# Flash_STM32.net
KiCad netlist of a schematic drawn in Altium Designer
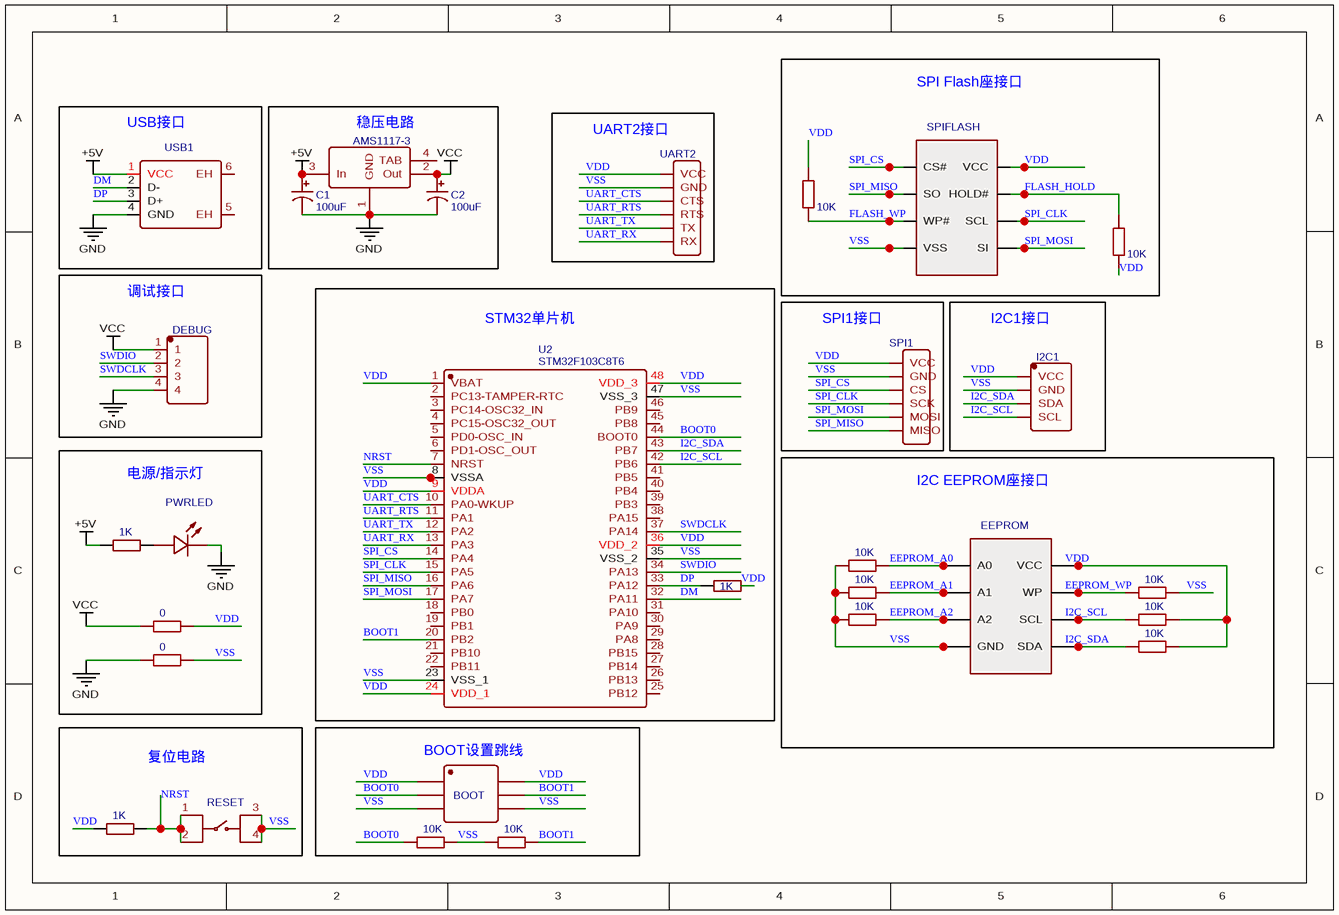
[diagram p0: Flash烧录器STM32版.schdoc]

(export (version "E")
  (design (tool "Eeschema 10.0.6"))
  (components
    (comp (ref "AMS1117-3")
      (value "AMS1117-3.3_C165482")
      (fields
        (field (name "BOM_SUPPLIER PART") "C165482")
        (field (name "BOM_MANUFACTURER PART") "AMS1117-3.3")
        (field (name "CONTRIBUTOR") "LCSC")
      )
      (libsource (lib "altium-import") (part "root_0_AMS1117-3.3_C165482_"))
    )
    (comp (ref "BOOT")
      (value "210S-2*3P L=11.6MMGold-plated black")
      (fields (field (name "BOM_SUPPLIER PART") "C124384") (field (name "CONTRIBUTOR") "LCSC"))
      (libsource (lib "altium-import") (part "root_0_210S-2*3P L=11.6MMGold-plated black_"))
    )
    (comp (ref "C1")
      (value "100uF")
      (fields
        (field (name "BOM_MANUFACTURER PART") "RVT1A101M0505")
        (field (name "BOM_SUPPLIER PART") "C3347")
      )
      (libsource (lib "altium-import") (part "root_0_100uF_"))
    )
    (comp (ref "C2")
      (value "100uF")
      (fields
        (field (name "BOM_MANUFACTURER PART") "RVT1A101M0505")
        (field (name "BOM_SUPPLIER PART") "C3347")
      )
      (libsource (lib "altium-import") (part "root_0_100uF_"))
    )
    (comp (ref "DEBUG")
      (value "MTP125-1104S1")
      (fields (field (name "BOM_SUPPLIER PART") "C358686") (field (name "CONTRIBUTOR") "LCSC"))
      (libsource (lib "altium-import") (part "root_0_MTP125-1104S1_"))
    )
    (comp (ref "EEPROM")
      (value "DS1009-08AT1NX-0A2")
      (fields (field (name "BOM_SUPPLIER PART") "C72124"))
      (libsource (lib "altium-import") (part "root_0_DS1009-08AT1NX-0A2_"))
    )
    (comp (ref "I2C1")
      (value "MTP125-1104S1")
      (fields (field (name "BOM_SUPPLIER PART") "C358686") (field (name "CONTRIBUTOR") "LCSC"))
      (libsource (lib "") (part "root_0_MTP125-1104S1__1"))
    )
    (comp (ref "PWRLED")
      (value "MHL3014SRTS")
      (fields (field (name "BOM_SUPPLIER PART") "C397053") (field (name "CONTRIBUTOR") "LCSC"))
      (libsource (lib "altium-import") (part "root_0_MHL3014SRTS_"))
    )
    (comp (ref "R1")
      (value "1K")
      (fields
        (field (name "BOM_MANUFACTURER PART") "0603WAF1001T5E")
        (field (name "BOM_SUPPLIER PART") "C21190")
      )
      (libsource (lib "altium-import") (part "root_0_1K_"))
    )
    (comp (ref "R2")
      (value "1K")
      (fields
        (field (name "BOM_MANUFACTURER PART") "0603WAF1001T5E")
        (field (name "BOM_SUPPLIER PART") "C21190")
      )
      (libsource (lib "altium-import") (part "root_0_1K_"))
    )
    (comp (ref "R3")
      (value "10K")
      (fields
        (field (name "BOM_SUPPLIER PART") "C237800")
        (field (name "BOM_MANUFACTURER PART") "RMCF1206JT10K0")
        (field (name "CONTRIBUTOR") "LCSC")
      )
      (libsource (lib "altium-import") (part "root_0_10K_"))
    )
    (comp (ref "R4")
      (value "10K")
      (fields
        (field (name "BOM_SUPPLIER PART") "C237800")
        (field (name "BOM_MANUFACTURER PART") "RMCF1206JT10K0")
        (field (name "CONTRIBUTOR") "LCSC")
      )
      (libsource (lib "altium-import") (part "root_0_10K_"))
    )
    (comp (ref "R5")
      (value "10K")
      (fields
        (field (name "BOM_SUPPLIER PART") "C237800")
        (field (name "BOM_MANUFACTURER PART") "RMCF1206JT10K0")
        (field (name "CONTRIBUTOR") "LCSC")
      )
      (libsource (lib "altium-import") (part "root_1_10K_"))
    )
    (comp (ref "R6")
      (value "10K")
      (fields
        (field (name "BOM_SUPPLIER PART") "C237800")
        (field (name "BOM_MANUFACTURER PART") "RMCF1206JT10K0")
        (field (name "CONTRIBUTOR") "LCSC")
      )
      (libsource (lib "altium-import") (part "root_1_10K_"))
    )
    (comp (ref "R7")
      (value "10K")
      (fields
        (field (name "BOM_SUPPLIER PART") "C237800")
        (field (name "BOM_MANUFACTURER PART") "RMCF1206JT10K0")
        (field (name "CONTRIBUTOR") "LCSC")
      )
      (libsource (lib "altium-import") (part "root_2_10K_"))
    )
    (comp (ref "R8")
      (value "10K")
      (fields
        (field (name "BOM_SUPPLIER PART") "C237800")
        (field (name "BOM_MANUFACTURER PART") "RMCF1206JT10K0")
        (field (name "CONTRIBUTOR") "LCSC")
      )
      (libsource (lib "altium-import") (part "root_2_10K_"))
    )
    (comp (ref "R9")
      (value "10K")
      (fields
        (field (name "BOM_SUPPLIER PART") "C237800")
        (field (name "BOM_MANUFACTURER PART") "RMCF1206JT10K0")
        (field (name "CONTRIBUTOR") "LCSC")
      )
      (libsource (lib "altium-import") (part "root_2_10K_"))
    )
    (comp (ref "R10")
      (value "10K")
      (fields
        (field (name "BOM_SUPPLIER PART") "C237800")
        (field (name "BOM_MANUFACTURER PART") "RMCF1206JT10K0")
        (field (name "CONTRIBUTOR") "LCSC")
      )
      (libsource (lib "altium-import") (part "root_2_10K_"))
    )
    (comp (ref "R11")
      (value "10K")
      (fields
        (field (name "BOM_SUPPLIER PART") "C237800")
        (field (name "BOM_MANUFACTURER PART") "RMCF1206JT10K0")
        (field (name "CONTRIBUTOR") "LCSC")
      )
      (libsource (lib "altium-import") (part "root_2_10K_"))
    )
    (comp (ref "R12")
      (value "10K")
      (fields
        (field (name "BOM_SUPPLIER PART") "C237800")
        (field (name "BOM_MANUFACTURER PART") "RMCF1206JT10K0")
        (field (name "CONTRIBUTOR") "LCSC")
      )
      (libsource (lib "altium-import") (part "root_2_10K_"))
    )
    (comp (ref "R13")
      (value "0")
      (fields
        (field (name "BOM_SUPPLIER PART") "C254574")
        (field (name "BOM_MANUFACTURER PART") "RM10FTN0")
        (field (name "CONTRIBUTOR") "LCSC")
      )
      (libsource (lib "altium-import") (part "root_0_0_"))
    )
    (comp (ref "R14")
      (value "0")
      (fields
        (field (name "BOM_SUPPLIER PART") "C254574")
        (field (name "BOM_MANUFACTURER PART") "RM10FTN0")
        (field (name "CONTRIBUTOR") "LCSC")
      )
      (libsource (lib "altium-import") (part "root_0_0_"))
    )
    (comp (ref "R15")
      (value "1K")
      (fields
        (field (name "BOM_MANUFACTURER PART") "0603WAF1001T5E")
        (field (name "BOM_SUPPLIER PART") "C21190")
      )
      (libsource (lib "altium-import") (part "root_0_1K_"))
    )
    (comp (ref "RESET")
      (value "K2-6639SP-C4SC-04")
      (fields (field (name "BOM_SUPPLIER PART") "C83206"))
      (libsource (lib "altium-import") (part "root_0_K2-6639SP-C4SC-04_"))
    )
    (comp (ref "SPI1")
      (value "Header-Male-2.54_1x6")
      (fields (field (name "BOM_SUPPLIER PART") "C37208"))
      (libsource (lib "altium-import") (part "root_0_Header-Male-2.54_1x6_"))
    )
    (comp (ref "SPIFLASH")
      (value "DS1009-08AT1NX-0A2")
      (fields (field (name "BOM_SUPPLIER PART") "C72124"))
      (libsource (lib "altium-import") (part "root_0_DS1009-08AT1NX-0A2_"))
    )
    (comp (ref "U2")
      (value "STM32F103C8T6")
      (fields (field (name "BOM_SUPPLIER PART") "C8734"))
      (libsource (lib "altium-import") (part "root_0_STM32F103C8T6_"))
    )
    (comp (ref "UART2")
      (value "Header-Male-2.54_1x6")
      (fields (field (name "BOM_SUPPLIER PART") "C37208"))
      (libsource (lib "altium-import") (part "root_0_Header-Male-2.54_1x6_"))
    )
    (comp (ref "USB1")
      (value "USB-05")
      (fields (field (name "BOM_SUPPLIER PART") "C112454") (field (name "CONTRIBUTOR") "LCSC"))
      (libsource (lib "altium-import") (part "root_0_USB-05_"))
    )
  )
  (nets
    (net (code "1") (name "+5V") (class "Default")
      (node (ref "AMS1117-3") (pin "3") (pinfunction "In_3") (pintype "passive"))
      (node (ref "C1") (pin "1") (pinfunction "1_1") (pintype "passive"))
      (node (ref "R1") (pin "1") (pinfunction "1_1") (pintype "passive"))
      (node (ref "USB1") (pin "1") (pinfunction "VCC_1") (pintype "passive"))
    )
    (net (code "2") (name "/BOOT0") (class "Default")
      (node (ref "BOOT") (pin "3") (pinfunction "3_3") (pintype "passive"))
      (node (ref "R3") (pin "1") (pinfunction "1_1") (pintype "passive"))
      (node (ref "U2") (pin "44") (pinfunction "BOOT0_44") (pintype "passive"))
    )
    (net (code "3") (name "/BOOT1") (class "Default")
      (node (ref "BOOT") (pin "4") (pinfunction "4_4") (pintype "passive"))
      (node (ref "R4") (pin "2") (pinfunction "2_2") (pintype "passive"))
      (node (ref "U2") (pin "20") (pinfunction "PB2_20") (pintype "passive"))
    )
    (net (code "4") (name "/DM") (class "Default")
      (node (ref "U2") (pin "32") (pinfunction "PA11_32") (pintype "passive"))
      (node (ref "USB1") (pin "2") (pinfunction "D-_2") (pintype "passive"))
    )
    (net (code "5") (name "/DP") (class "Default")
      (node (ref "R15") (pin "1") (pinfunction "1_1") (pintype "passive"))
      (node (ref "U2") (pin "33") (pinfunction "PA12_33") (pintype "passive"))
      (node (ref "USB1") (pin "3") (pinfunction "D+_3") (pintype "passive"))
    )
    (net (code "6") (name "/EEPROM_A0") (class "Default")
      (node (ref "EEPROM") (pin "1") (pinfunction "CS#_1") (pintype "passive"))
      (node (ref "R8") (pin "1") (pinfunction "1_1") (pintype "passive"))
    )
    (net (code "7") (name "/EEPROM_A1") (class "Default")
      (node (ref "EEPROM") (pin "2") (pinfunction "SO_2") (pintype "passive"))
      (node (ref "R11") (pin "1") (pinfunction "1_1") (pintype "passive"))
    )
    (net (code "8") (name "/EEPROM_A2") (class "Default")
      (node (ref "EEPROM") (pin "3") (pinfunction "WP#_3") (pintype "passive"))
      (node (ref "R12") (pin "1") (pinfunction "1_1") (pintype "passive"))
    )
    (net (code "9") (name "/EEPROM_WP") (class "Default")
      (node (ref "EEPROM") (pin "7") (pinfunction "HOLD#_7") (pintype "passive"))
      (node (ref "R10") (pin "2") (pinfunction "2_2") (pintype "passive"))
    )
    (net (code "10") (name "/FLASH_HOLD") (class "Default")
      (node (ref "R6") (pin "2") (pinfunction "2_2") (pintype "passive"))
      (node (ref "SPIFLASH") (pin "7") (pinfunction "HOLD#_7") (pintype "passive"))
    )
    (net (code "11") (name "/FLASH_WP") (class "Default")
      (node (ref "R5") (pin "1") (pinfunction "1_1") (pintype "passive"))
      (node (ref "SPIFLASH") (pin "3") (pinfunction "WP#_3") (pintype "passive"))
    )
    (net (code "12") (name "/I2C_SCL") (class "Default")
      (node (ref "EEPROM") (pin "6") (pinfunction "SCL_6") (pintype "passive"))
      (node (ref "I2C1") (pin "4") (pinfunction "SCL_4") (pintype "passive"))
      (node (ref "R9") (pin "2") (pinfunction "2_2") (pintype "passive"))
      (node (ref "U2") (pin "42") (pinfunction "PB6_42") (pintype "passive"))
    )
    (net (code "13") (name "/I2C_SDA") (class "Default")
      (node (ref "EEPROM") (pin "5") (pinfunction "SI_5") (pintype "passive"))
      (node (ref "I2C1") (pin "3") (pinfunction "SDA_3") (pintype "passive"))
      (node (ref "R7") (pin "2") (pinfunction "2_2") (pintype "passive"))
      (node (ref "U2") (pin "43") (pinfunction "PB7_43") (pintype "passive"))
    )
    (net (code "14") (name "/NRST") (class "Default")
      (node (ref "R2") (pin "2") (pinfunction "2_2") (pintype "passive"))
      (node (ref "RESET") (pin "1") (pinfunction "1_1") (pintype "passive"))
      (node (ref "RESET") (pin "2") (pinfunction "2_2") (pintype "passive"))
      (node (ref "U2") (pin "7") (pinfunction "NRST_7") (pintype "passive"))
    )
    (net (code "15") (name "/SPI_CLK") (class "Default")
      (node (ref "SPI1") (pin "4") (pinfunction "RTS_4") (pintype "passive"))
      (node (ref "SPIFLASH") (pin "6") (pinfunction "SCL_6") (pintype "passive"))
      (node (ref "U2") (pin "15") (pinfunction "PA5_15") (pintype "passive"))
    )
    (net (code "16") (name "/SPI_CS") (class "Default")
      (node (ref "SPI1") (pin "3") (pinfunction "CTS_3") (pintype "passive"))
      (node (ref "SPIFLASH") (pin "1") (pinfunction "CS#_1") (pintype "passive"))
      (node (ref "U2") (pin "14") (pinfunction "PA4_14") (pintype "passive"))
    )
    (net (code "17") (name "/SPI_MISO") (class "Default")
      (node (ref "SPI1") (pin "6") (pinfunction "RX_6") (pintype "passive"))
      (node (ref "SPIFLASH") (pin "2") (pinfunction "SO_2") (pintype "passive"))
      (node (ref "U2") (pin "16") (pinfunction "PA6_16") (pintype "passive"))
    )
    (net (code "18") (name "/SPI_MOSI") (class "Default")
      (node (ref "SPI1") (pin "5") (pinfunction "TX_5") (pintype "passive"))
      (node (ref "SPIFLASH") (pin "5") (pinfunction "SI_5") (pintype "passive"))
      (node (ref "U2") (pin "17") (pinfunction "PA7_17") (pintype "passive"))
    )
    (net (code "19") (name "/SWDCLK") (class "Default")
      (node (ref "DEBUG") (pin "3") (pinfunction "3_3") (pintype "passive"))
      (node (ref "U2") (pin "37") (pinfunction "PA14_37") (pintype "passive"))
    )
    (net (code "20") (name "/SWDIO") (class "Default")
      (node (ref "DEBUG") (pin "2") (pinfunction "2_2") (pintype "passive"))
      (node (ref "U2") (pin "34") (pinfunction "PA13_34") (pintype "passive"))
    )
    (net (code "21") (name "/UART_CTS") (class "Default")
      (node (ref "U2") (pin "10") (pinfunction "PA0-WKUP_10") (pintype "passive"))
      (node (ref "UART2") (pin "3") (pinfunction "CTS_3") (pintype "passive"))
    )
    (net (code "22") (name "/UART_RTS") (class "Default")
      (node (ref "U2") (pin "11") (pinfunction "PA1_11") (pintype "passive"))
      (node (ref "UART2") (pin "4") (pinfunction "RTS_4") (pintype "passive"))
    )
    (net (code "23") (name "/UART_RX") (class "Default")
      (node (ref "U2") (pin "13") (pinfunction "PA3_13") (pintype "passive"))
      (node (ref "UART2") (pin "6") (pinfunction "RX_6") (pintype "passive"))
    )
    (net (code "24") (name "/UART_TX") (class "Default")
      (node (ref "U2") (pin "12") (pinfunction "PA2_12") (pintype "passive"))
      (node (ref "UART2") (pin "5") (pinfunction "TX_5") (pintype "passive"))
    )
    (net (code "25") (name "/VDD") (class "Default")
      (node (ref "BOOT") (pin "1") (pinfunction "1_1") (pintype "passive"))
      (node (ref "BOOT") (pin "2") (pinfunction "2_2") (pintype "passive"))
      (node (ref "EEPROM") (pin "8") (pinfunction "VCC_8") (pintype "passive"))
      (node (ref "I2C1") (pin "1") (pinfunction "VCC_1") (pintype "passive"))
      (node (ref "R13") (pin "2") (pinfunction "2_2") (pintype "passive"))
      (node (ref "R15") (pin "2") (pinfunction "2_2") (pintype "passive"))
      (node (ref "R2") (pin "1") (pinfunction "1_1") (pintype "passive"))
      (node (ref "R5") (pin "2") (pinfunction "2_2") (pintype "passive"))
      (node (ref "R6") (pin "1") (pinfunction "1_1") (pintype "passive"))
      (node (ref "R7") (pin "1") (pinfunction "1_1") (pintype "passive"))
      (node (ref "R9") (pin "1") (pinfunction "1_1") (pintype "passive"))
      (node (ref "SPI1") (pin "1") (pinfunction "VCC_1") (pintype "passive"))
      (node (ref "SPIFLASH") (pin "8") (pinfunction "VCC_8") (pintype "passive"))
      (node (ref "U2") (pin "1") (pinfunction "VBAT_1") (pintype "passive"))
      (node (ref "U2") (pin "24") (pinfunction "VDD_1_24") (pintype "passive"))
      (node (ref "U2") (pin "36") (pinfunction "VDD_2_36") (pintype "passive"))
      (node (ref "U2") (pin "48") (pinfunction "VDD_3_48") (pintype "passive"))
      (node (ref "U2") (pin "9") (pinfunction "VDDA_9") (pintype "passive"))
      (node (ref "UART2") (pin "1") (pinfunction "VCC_1") (pintype "passive"))
    )
    (net (code "26") (name "/VSS") (class "Default")
      (node (ref "BOOT") (pin "5") (pinfunction "5_5") (pintype "passive"))
      (node (ref "BOOT") (pin "6") (pinfunction "6_6") (pintype "passive"))
      (node (ref "EEPROM") (pin "4") (pinfunction "VSS_4") (pintype "passive"))
      (node (ref "I2C1") (pin "2") (pinfunction "GND_2") (pintype "passive"))
      (node (ref "R10") (pin "1") (pinfunction "1_1") (pintype "passive"))
      (node (ref "R11") (pin "2") (pinfunction "2_2") (pintype "passive"))
      (node (ref "R12") (pin "2") (pinfunction "2_2") (pintype "passive"))
      (node (ref "R14") (pin "2") (pinfunction "2_2") (pintype "passive"))
      (node (ref "R3") (pin "2") (pinfunction "2_2") (pintype "passive"))
      (node (ref "R4") (pin "1") (pinfunction "1_1") (pintype "passive"))
      (node (ref "R8") (pin "2") (pinfunction "2_2") (pintype "passive"))
      (node (ref "RESET") (pin "3") (pinfunction "3_3") (pintype "passive"))
      (node (ref "RESET") (pin "4") (pinfunction "4_4") (pintype "passive"))
      (node (ref "SPI1") (pin "2") (pinfunction "GND_2") (pintype "passive"))
      (node (ref "SPIFLASH") (pin "4") (pinfunction "VSS_4") (pintype "passive"))
      (node (ref "U2") (pin "23") (pinfunction "VSS_1_23") (pintype "passive"))
      (node (ref "U2") (pin "35") (pinfunction "VSS_2_35") (pintype "passive"))
      (node (ref "U2") (pin "47") (pinfunction "VSS_3_47") (pintype "passive"))
      (node (ref "U2") (pin "8") (pinfunction "VSSA_8") (pintype "passive"))
      (node (ref "UART2") (pin "2") (pinfunction "GND_2") (pintype "passive"))
    )
    (net (code "27") (name "GND") (class "Default")
      (node (ref "AMS1117-3") (pin "1") (pinfunction "GND_1") (pintype "passive"))
      (node (ref "C1") (pin "2") (pinfunction "2_2") (pintype "passive"))
      (node (ref "C2") (pin "2") (pinfunction "2_2") (pintype "passive"))
      (node (ref "DEBUG") (pin "4") (pinfunction "4_4") (pintype "passive"))
      (node (ref "PWRLED") (pin "2") (pinfunction "K_2") (pintype "passive"))
      (node (ref "R14") (pin "1") (pinfunction "1_1") (pintype "passive"))
      (node (ref "USB1") (pin "4") (pinfunction "GND_4") (pintype "passive"))
    )
    (net (code "28") (name "Net-(PWRLED-A)") (class "Default")
      (node (ref "PWRLED") (pin "1") (pinfunction "A_1") (pintype "passive"))
      (node (ref "R1") (pin "2") (pinfunction "2_2") (pintype "passive"))
    )
    (net (code "29") (name "VCC") (class "Default")
      (node (ref "AMS1117-3") (pin "2") (pinfunction "Out_2") (pintype "passive"))
      (node (ref "C2") (pin "1") (pinfunction "1_1") (pintype "passive"))
      (node (ref "DEBUG") (pin "1") (pinfunction "1_1") (pintype "passive"))
      (node (ref "R13") (pin "1") (pinfunction "1_1") (pintype "passive"))
    )
    (net (code "30") (name "unconnected-(AMS1117-3-TAB-Pad4)") (class "Default")
      (node (ref "AMS1117-3") (pin "4") (pinfunction "TAB_4") (pintype "passive"))
    )
    (net (code "31") (name "unconnected-(U2-PA8-Pad29)") (class "Default")
      (node (ref "U2") (pin "29") (pinfunction "PA8_29") (pintype "passive"))
    )
    (net (code "32") (name "unconnected-(U2-PA9-Pad30)") (class "Default")
      (node (ref "U2") (pin "30") (pinfunction "PA9_30") (pintype "passive"))
    )
    (net (code "33") (name "unconnected-(U2-PA10-Pad31)") (class "Default")
      (node (ref "U2") (pin "31") (pinfunction "PA10_31") (pintype "passive"))
    )
    (net (code "34") (name "unconnected-(U2-PA15-Pad38)") (class "Default")
      (node (ref "U2") (pin "38") (pinfunction "PA15_38") (pintype "passive"))
    )
    (net (code "35") (name "unconnected-(U2-PB0-Pad18)") (class "Default")
      (node (ref "U2") (pin "18") (pinfunction "PB0_18") (pintype "passive"))
    )
    (net (code "36") (name "unconnected-(U2-PB1-Pad19)") (class "Default")
      (node (ref "U2") (pin "19") (pinfunction "PB1_19") (pintype "passive"))
    )
    (net (code "37") (name "unconnected-(U2-PB3-Pad39)") (class "Default")
      (node (ref "U2") (pin "39") (pinfunction "PB3_39") (pintype "passive"))
    )
    (net (code "38") (name "unconnected-(U2-PB4-Pad40)") (class "Default")
      (node (ref "U2") (pin "40") (pinfunction "PB4_40") (pintype "passive"))
    )
    (net (code "39") (name "unconnected-(U2-PB5-Pad41)") (class "Default")
      (node (ref "U2") (pin "41") (pinfunction "PB5_41") (pintype "passive"))
    )
    (net (code "40") (name "unconnected-(U2-PB8-Pad45)") (class "Default")
      (node (ref "U2") (pin "45") (pinfunction "PB8_45") (pintype "passive"))
    )
    (net (code "41") (name "unconnected-(U2-PB9-Pad46)") (class "Default")
      (node (ref "U2") (pin "46") (pinfunction "PB9_46") (pintype "passive"))
    )
    (net (code "42") (name "unconnected-(U2-PB10-Pad21)") (class "Default")
      (node (ref "U2") (pin "21") (pinfunction "PB10_21") (pintype "passive"))
    )
    (net (code "43") (name "unconnected-(U2-PB11-Pad22)") (class "Default")
      (node (ref "U2") (pin "22") (pinfunction "PB11_22") (pintype "passive"))
    )
    (net (code "44") (name "unconnected-(U2-PB12-Pad25)") (class "Default")
      (node (ref "U2") (pin "25") (pinfunction "PB12_25") (pintype "passive"))
    )
    (net (code "45") (name "unconnected-(U2-PB13-Pad26)") (class "Default")
      (node (ref "U2") (pin "26") (pinfunction "PB13_26") (pintype "passive"))
    )
    (net (code "46") (name "unconnected-(U2-PB14-Pad27)") (class "Default")
      (node (ref "U2") (pin "27") (pinfunction "PB14_27") (pintype "passive"))
    )
    (net (code "47") (name "unconnected-(U2-PB15-Pad28)") (class "Default")
      (node (ref "U2") (pin "28") (pinfunction "PB15_28") (pintype "passive"))
    )
    (net (code "48") (name "unconnected-(U2-PC13-TAMPER-RTC-Pad2)") (class "Default")
      (node (ref "U2") (pin "2") (pinfunction "PC13-TAMPER-RTC_2") (pintype "passive"))
    )
    (net (code "49") (name "unconnected-(U2-PC14-OSC32_IN-Pad3)") (class "Default")
      (node (ref "U2") (pin "3") (pinfunction "PC14-OSC32_IN_3") (pintype "passive"))
    )
    (net (code "50") (name "unconnected-(U2-PC15-OSC32_OUT-Pad4)") (class "Default")
      (node (ref "U2") (pin "4") (pinfunction "PC15-OSC32_OUT_4") (pintype "passive"))
    )
    (net (code "51") (name "unconnected-(U2-PD0-OSC_IN-Pad5)") (class "Default")
      (node (ref "U2") (pin "5") (pinfunction "PD0-OSC_IN_5") (pintype "passive"))
    )
    (net (code "52") (name "unconnected-(U2-PD1-OSC_OUT-Pad6)") (class "Default")
      (node (ref "U2") (pin "6") (pinfunction "PD1-OSC_OUT_6") (pintype "passive"))
    )
    (net (code "53") (name "unconnected-(USB1-EH-Pad5)") (class "Default")
      (node (ref "USB1") (pin "5") (pinfunction "EH_5") (pintype "passive"))
    )
    (net (code "54") (name "unconnected-(USB1-EH-Pad6)") (class "Default")
      (node (ref "USB1") (pin "6") (pinfunction "EH_6") (pintype "passive"))
    )
  )
)
